# 3_POWER.net
KiCad netlist of a schematic drawn in Altium Designer
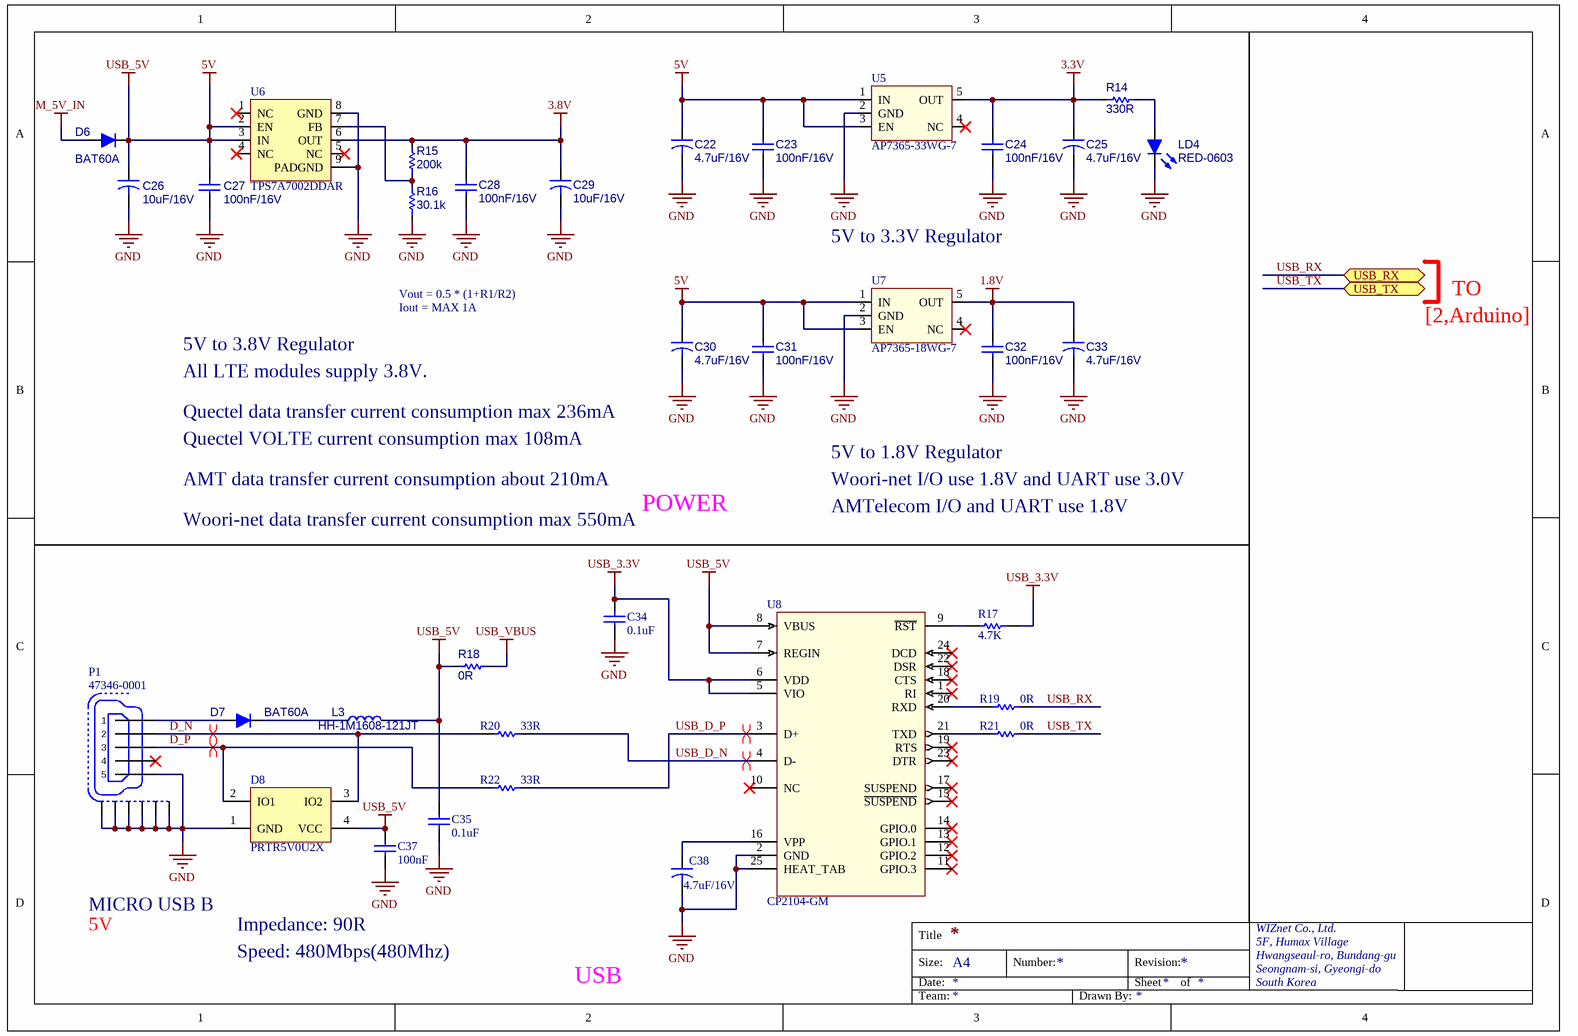
[diagram p0: 3.POWER.SchDoc]

(export (version "E")
  (design (tool "Eeschema 10.0.6"))
  (components
    (comp (ref "C22")
      (value "4.7uF/16V")
      (footprint "CAP-A Size")
      (description "Tantal CAP A Size EIA/IECQ 3216")
      (libsource (lib "Scott_lib") (part "CAP-A Size"))
    )
    (comp (ref "C23")
      (value "100nF/16V")
      (footprint "CAP-0603")
      (description "Ceramic CAP 0603(1608)")
      (libsource (lib "Scott_lib") (part "CAP-0603"))
    )
    (comp (ref "C24")
      (value "100nF/16V")
      (footprint "CAP-0603")
      (description "Ceramic CAP 0603(1608)")
      (libsource (lib "Scott_lib") (part "CAP-0603"))
    )
    (comp (ref "C25")
      (value "4.7uF/16V")
      (footprint "CAP-A Size")
      (description "Tantal CAP A Size EIA/IECQ 3216")
      (libsource (lib "Scott_lib") (part "CAP-A Size"))
    )
    (comp (ref "C26")
      (value "10uF/16V")
      (footprint "CAP-A Size")
      (description "Tantal CAP A Size EIA/IECQ 3216")
      (libsource (lib "Scott_lib") (part "CAP-A Size"))
    )
    (comp (ref "C27")
      (value "100nF/16V")
      (footprint "CAP-0603")
      (description "Ceramic CAP 0603(1608)")
      (libsource (lib "Scott_lib") (part "CAP-0603"))
    )
    (comp (ref "C28")
      (value "100nF/16V")
      (footprint "CAP-0603")
      (description "Ceramic CAP 0603(1608)")
      (libsource (lib "Scott_lib") (part "CAP-0603"))
    )
    (comp (ref "C29")
      (value "10uF/16V")
      (footprint "CAP-A Size")
      (description "Tantal CAP A Size EIA/IECQ 3216")
      (libsource (lib "Scott_lib") (part "CAP-A Size"))
    )
    (comp (ref "C30")
      (value "4.7uF/16V")
      (footprint "CAP-A Size")
      (description "Tantal CAP A Size EIA/IECQ 3216")
      (libsource (lib "Scott_lib") (part "CAP-A Size"))
    )
    (comp (ref "C31")
      (value "100nF/16V")
      (footprint "CAP-0603")
      (description "Ceramic CAP 0603(1608)")
      (libsource (lib "Scott_lib") (part "CAP-0603"))
    )
    (comp (ref "C32")
      (value "100nF/16V")
      (footprint "CAP-0603")
      (description "Ceramic CAP 0603(1608)")
      (libsource (lib "Scott_lib") (part "CAP-0603"))
    )
    (comp (ref "C33")
      (value "4.7uF/16V")
      (footprint "CAP-A Size")
      (description "Tantal CAP A Size EIA/IECQ 3216")
      (libsource (lib "Scott_lib") (part "CAP-A Size"))
    )
    (comp (ref "C34")
      (value "0.1uF")
      (footprint "CAP-0603")
      (description "Ceramic CAP 0603(1608)")
      (libsource (lib "Scott_lib") (part "CAP-0603"))
    )
    (comp (ref "C35")
      (value "0.1uF")
      (footprint "CAP-0603")
      (description "Ceramic CAP 0603(1608)")
      (libsource (lib "Scott_lib") (part "CAP-0603"))
    )
    (comp (ref "C37")
      (value "100nF")
      (footprint "CAP-0603")
      (description "Ceramic CAP 0603(1608)")
      (libsource (lib "Scott_lib") (part "CAP-0603"))
    )
    (comp (ref "C38")
      (value "4.7uF/16V")
      (footprint "CAP-A Size")
      (description "Tantla CAP A Size EIA/IECQ 3216")
      (libsource (lib "Scott_lib") (part "CAP-A Size"))
    )
    (comp (ref "D6")
      (value "BAT60A")
      (footprint "SOD-323(1-C,2-A)")
      (description "Silicon Schottky Diode")
      (libsource (lib "Scott_lib") (part "DIODE-BAT60A"))
    )
    (comp (ref "D7")
      (value "BAT60A")
      (footprint "SOD-323(1-C,2-A)")
      (description "Silicon Schottky Diode")
      (libsource (lib "Scott_lib") (part "DIODE-BAT60A"))
    )
    (comp (ref "D8")
      (value "PRTR5V0U2X")
      (footprint "SOT-143")
      (description "Ultra low capacitance double rail-to-rail ESD protection diode")
      (fields
        (field (name "MANUFACTURER") "NXP")
        (field (name "2ND SOURCE PART NUMBER") "152-4157")
        (field (name "PUBLISHER") "Nordic Semiconductor")
      )
      (libsource (lib "Quectel_IF_Board") (part "PRTR5V0U2X"))
    )
    (comp (ref "L3")
      (value "HH-1M1608-121JT")
      (footprint "IND-0603")
      (description "Inductor 0603(1608)")
      (libsource (lib "Scott_lib") (part "IND-0603"))
    )
    (comp (ref "LD4")
      (value "RED-0603")
      (footprint "LED-0603-RED")
      (description "LED-0603")
      (libsource (lib "Scott_lib") (part "LED-0603"))
    )
    (comp (ref "P1")
      (value "47346-0001")
      (footprint "USB-MOLEX-47346")
      (description "MICRO USB B Type")
      (libsource (lib "Edward") (part "47346-0001"))
    )
    (comp (ref "R14")
      (value "330R")
      (footprint "RES-0402")
      (description "RES-0402")
      (libsource (lib "Scott_lib") (part "RES-0402"))
    )
    (comp (ref "R15")
      (value "200k")
      (footprint "RES-0603")
      (description "RES0603")
      (libsource (lib "") (part "RES-0603_1"))
    )
    (comp (ref "R16")
      (value "30.1k")
      (footprint "RES-0603")
      (description "RES0603")
      (libsource (lib "") (part "RES-0603_1"))
    )
    (comp (ref "R17")
      (value "4.7K")
      (footprint "RES-0603")
      (description "RES-0603")
      (libsource (lib "Scott_lib") (part "RES-0603"))
    )
    (comp (ref "R18")
      (value "0R")
      (footprint "RES-0402")
      (description "RES-0402")
      (libsource (lib "Scott_lib") (part "RES-0402"))
    )
    (comp (ref "R19")
      (value "0R")
      (footprint "RES-0603")
      (description "RES-0603")
      (libsource (lib "Scott_lib") (part "RES-0603"))
    )
    (comp (ref "R20")
      (value "33R")
      (footprint "RES-0603")
      (description "RES-0603")
      (libsource (lib "Scott_lib") (part "RES-0603"))
    )
    (comp (ref "R21")
      (value "0R")
      (footprint "RES-0603")
      (description "RES-0603")
      (libsource (lib "Scott_lib") (part "RES-0603"))
    )
    (comp (ref "R22")
      (value "33R")
      (footprint "RES-0603")
      (description "RES-0603")
      (libsource (lib "Scott_lib") (part "RES-0603"))
    )
    (comp (ref "U5")
      (value "AP7365-33WG-7")
      (footprint "SOT-25")
      (description "3.3V 600mA Regulator/SOT25(Fixed Output)")
      (libsource (lib "Edward") (part "AP7365-33WG-7"))
    )
    (comp (ref "U6")
      (value "TPS7A7002DDAR")
      (footprint "SO-08-EP")
      (libsource (lib "Edward") (part "TPS7A7002DDAR"))
    )
    (comp (ref "U7")
      (value "AP7365-18WG-7")
      (footprint "SOT-25")
      (description "3.3V 600mA Regulator/SOT25(Fixed Output)")
      (libsource (lib "Edward") (part "AP7365-33WG-7"))
    )
    (comp (ref "U8")
      (value "CP2104-GM")
      (footprint "QFN24(0.5/4X4)")
      (description "USB to UART Bridge, SiliconLabs")
      (libsource (lib "Edward") (part "CP2104-GM"))
    )
  )
  (nets
    (net (code "1") (name "/D_N") (class "Default")
      (node (ref "D8") (pin "3") (pinfunction "IO2_3") (pintype "passive"))
      (node (ref "P1") (pin "2") (pinfunction "2_2") (pintype "passive"))
      (node (ref "R20") (pin "1") (pinfunction "1_1") (pintype "passive"))
    )
    (net (code "2") (name "/D_P") (class "Default")
      (node (ref "D8") (pin "2") (pinfunction "IO1_2") (pintype "passive"))
      (node (ref "P1") (pin "3") (pinfunction "3_3") (pintype "passive"))
      (node (ref "R22") (pin "1") (pinfunction "1_1") (pintype "passive"))
    )
    (net (code "3") (name "/USB_D_N") (class "Default")
      (node (ref "R20") (pin "2") (pinfunction "2_2") (pintype "passive"))
      (node (ref "U8") (pin "4") (pinfunction "D-_4") (pintype "passive"))
    )
    (net (code "4") (name "/USB_D_P") (class "Default")
      (node (ref "R22") (pin "2") (pinfunction "2_2") (pintype "passive"))
      (node (ref "U8") (pin "3") (pinfunction "D+_3") (pintype "passive"))
    )
    (net (code "5") (name "/USB_RX") (class "Default")
      (node (ref "R19") (pin "2") (pinfunction "2_2") (pintype "passive"))
    )
    (net (code "6") (name "/USB_TX") (class "Default")
      (node (ref "R21") (pin "2") (pinfunction "2_2") (pintype "passive"))
    )
    (net (code "7") (name "1.8V") (class "Default")
      (node (ref "C32") (pin "2") (pinfunction "2_2") (pintype "passive"))
      (node (ref "C33") (pin "1") (pinfunction "1_1") (pintype "passive"))
      (node (ref "U7") (pin "5") (pinfunction "OUT_5") (pintype "passive"))
    )
    (net (code "8") (name "3.3V") (class "Default")
      (node (ref "C24") (pin "2") (pinfunction "2_2") (pintype "passive"))
      (node (ref "C25") (pin "1") (pinfunction "1_1") (pintype "passive"))
      (node (ref "R14") (pin "1") (pinfunction "1_1") (pintype "passive"))
      (node (ref "U5") (pin "5") (pinfunction "OUT_5") (pintype "passive"))
    )
    (net (code "9") (name "3.8V") (class "Default")
      (node (ref "C28") (pin "2") (pinfunction "2_2") (pintype "passive"))
      (node (ref "C29") (pin "1") (pinfunction "1_1") (pintype "passive"))
      (node (ref "R15") (pin "2") (pinfunction "2_2") (pintype "passive"))
      (node (ref "U6") (pin "6") (pinfunction "OUT_6") (pintype "passive"))
    )
    (net (code "10") (name "5V") (class "Default")
      (node (ref "C22") (pin "1") (pinfunction "1_1") (pintype "passive"))
      (node (ref "C23") (pin "2") (pinfunction "2_2") (pintype "passive"))
      (node (ref "C26") (pin "1") (pinfunction "1_1") (pintype "passive"))
      (node (ref "C27") (pin "2") (pinfunction "2_2") (pintype "passive"))
      (node (ref "C30") (pin "1") (pinfunction "1_1") (pintype "passive"))
      (node (ref "C31") (pin "2") (pinfunction "2_2") (pintype "passive"))
      (node (ref "C35") (pin "2") (pinfunction "2_2") (pintype "passive"))
      (node (ref "C37") (pin "2") (pinfunction "2_2") (pintype "passive"))
      (node (ref "D6") (pin "1") (pinfunction "K_1") (pintype "passive"))
      (node (ref "D8") (pin "4") (pinfunction "VCC_4") (pintype "passive"))
      (node (ref "L3") (pin "2") (pinfunction "2_2") (pintype "passive"))
      (node (ref "R18") (pin "1") (pinfunction "1_1") (pintype "passive"))
      (node (ref "U5") (pin "1") (pinfunction "IN_1") (pintype "passive"))
      (node (ref "U5") (pin "3") (pinfunction "EN_3") (pintype "passive"))
      (node (ref "U6") (pin "2") (pinfunction "EN_2") (pintype "passive"))
      (node (ref "U6") (pin "3") (pinfunction "IN_3") (pintype "passive"))
      (node (ref "U7") (pin "1") (pinfunction "IN_1") (pintype "passive"))
      (node (ref "U7") (pin "3") (pinfunction "EN_3") (pintype "passive"))
      (node (ref "U8") (pin "7") (pinfunction "REGIN_7") (pintype "input"))
      (node (ref "U8") (pin "8") (pinfunction "VBUS_8") (pintype "input"))
    )
    (net (code "11") (name "GND") (class "Default")
      (node (ref "C22") (pin "2") (pinfunction "2_2") (pintype "passive"))
      (node (ref "C23") (pin "1") (pinfunction "1_1") (pintype "passive"))
      (node (ref "C24") (pin "1") (pinfunction "1_1") (pintype "passive"))
      (node (ref "C25") (pin "2") (pinfunction "2_2") (pintype "passive"))
      (node (ref "C26") (pin "2") (pinfunction "2_2") (pintype "passive"))
      (node (ref "C27") (pin "1") (pinfunction "1_1") (pintype "passive"))
      (node (ref "C28") (pin "1") (pinfunction "1_1") (pintype "passive"))
      (node (ref "C29") (pin "2") (pinfunction "2_2") (pintype "passive"))
      (node (ref "C30") (pin "2") (pinfunction "2_2") (pintype "passive"))
      (node (ref "C31") (pin "1") (pinfunction "1_1") (pintype "passive"))
      (node (ref "C32") (pin "1") (pinfunction "1_1") (pintype "passive"))
      (node (ref "C33") (pin "2") (pinfunction "2_2") (pintype "passive"))
      (node (ref "C34") (pin "1") (pinfunction "1_1") (pintype "passive"))
      (node (ref "C35") (pin "1") (pinfunction "1_1") (pintype "passive"))
      (node (ref "C37") (pin "1") (pinfunction "1_1") (pintype "passive"))
      (node (ref "C38") (pin "2") (pinfunction "2_2") (pintype "passive"))
      (node (ref "D8") (pin "1") (pinfunction "GND_1") (pintype "passive"))
      (node (ref "LD4") (pin "2") (pinfunction "K_2") (pintype "passive"))
      (node (ref "P1") (pin "10") (pinfunction "10_10") (pintype "passive"))
      (node (ref "P1") (pin "11") (pinfunction "11_11") (pintype "passive"))
      (node (ref "P1") (pin "5") (pinfunction "5_5") (pintype "passive"))
      (node (ref "P1") (pin "6") (pinfunction "6_6") (pintype "passive"))
      (node (ref "P1") (pin "7") (pinfunction "7_7") (pintype "passive"))
      (node (ref "P1") (pin "8") (pinfunction "8_8") (pintype "passive"))
      (node (ref "P1") (pin "9") (pinfunction "9_9") (pintype "passive"))
      (node (ref "R16") (pin "1") (pinfunction "1_1") (pintype "passive"))
      (node (ref "U5") (pin "2") (pinfunction "GND_2") (pintype "passive"))
      (node (ref "U6") (pin "8") (pinfunction "GND_8") (pintype "passive"))
      (node (ref "U6") (pin "9") (pinfunction "PADGND_9") (pintype "passive"))
      (node (ref "U7") (pin "2") (pinfunction "GND_2") (pintype "passive"))
      (node (ref "U8") (pin "2") (pinfunction "GND_2") (pintype "power_in"))
      (node (ref "U8") (pin "25") (pinfunction "HEAT_TAB_25") (pintype "passive"))
    )
    (net (code "12") (name "M_5V_IN") (class "Default")
      (node (ref "D6") (pin "2") (pinfunction "A_2") (pintype "passive"))
    )
    (net (code "13") (name "Net-(D7-A)") (class "Default")
      (node (ref "D7") (pin "2") (pinfunction "A_2") (pintype "passive"))
      (node (ref "P1") (pin "1") (pinfunction "1_1") (pintype "passive"))
    )
    (net (code "14") (name "Net-(D7-K)") (class "Default")
      (node (ref "D7") (pin "1") (pinfunction "K_1") (pintype "passive"))
      (node (ref "L3") (pin "1") (pinfunction "1_1") (pintype "passive"))
    )
    (net (code "15") (name "Net-(LD4-A)") (class "Default")
      (node (ref "LD4") (pin "1") (pinfunction "A_1") (pintype "passive"))
      (node (ref "R14") (pin "2") (pinfunction "2_2") (pintype "passive"))
    )
    (net (code "16") (name "Net-(U6-FB)") (class "Default")
      (node (ref "R15") (pin "1") (pinfunction "1_1") (pintype "passive"))
      (node (ref "R16") (pin "2") (pinfunction "2_2") (pintype "passive"))
      (node (ref "U6") (pin "7") (pinfunction "FB_7") (pintype "passive"))
    )
    (net (code "17") (name "Net-(U8-RST)") (class "Default")
      (node (ref "R17") (pin "1") (pinfunction "1_1") (pintype "passive"))
      (node (ref "U8") (pin "9") (pinfunction "RST_9") (pintype "passive"))
    )
    (net (code "18") (name "Net-(U8-RXD)") (class "Default")
      (node (ref "R19") (pin "1") (pinfunction "1_1") (pintype "passive"))
      (node (ref "U8") (pin "20") (pinfunction "RXD_20") (pintype "input"))
    )
    (net (code "19") (name "Net-(U8-TXD)") (class "Default")
      (node (ref "R21") (pin "1") (pinfunction "1_1") (pintype "passive"))
      (node (ref "U8") (pin "21") (pinfunction "TXD_21") (pintype "output"))
    )
    (net (code "20") (name "Net-(U8-VPP)") (class "Default")
      (node (ref "C38") (pin "1") (pinfunction "1_1") (pintype "passive"))
      (node (ref "U8") (pin "16") (pinfunction "VPP_16") (pintype "passive"))
    )
    (net (code "21") (name "USB_3.3V") (class "Default")
      (node (ref "C34") (pin "2") (pinfunction "2_2") (pintype "passive"))
      (node (ref "R17") (pin "2") (pinfunction "2_2") (pintype "passive"))
      (node (ref "U8") (pin "5") (pinfunction "VIO_5") (pintype "power_in"))
      (node (ref "U8") (pin "6") (pinfunction "VDD_6") (pintype "power_in"))
    )
    (net (code "22") (name "USB_VBUS") (class "Default")
      (node (ref "R18") (pin "2") (pinfunction "2_2") (pintype "passive"))
    )
    (net (code "23") (name "unconnected-(P1-Pad4)") (class "Default")
      (node (ref "P1") (pin "4") (pinfunction "4_4") (pintype "passive+no_connect"))
    )
    (net (code "24") (name "unconnected-(U5-NC-Pad4)") (class "Default")
      (node (ref "U5") (pin "4") (pinfunction "NC_4") (pintype "passive+no_connect"))
    )
    (net (code "25") (name "unconnected-(U6-NC-Pad1)") (class "Default")
      (node (ref "U6") (pin "1") (pinfunction "NC_1") (pintype "passive+no_connect"))
    )
    (net (code "26") (name "unconnected-(U6-NC-Pad4)") (class "Default")
      (node (ref "U6") (pin "4") (pinfunction "NC_4") (pintype "passive+no_connect"))
    )
    (net (code "27") (name "unconnected-(U6-NC-Pad5)") (class "Default")
      (node (ref "U6") (pin "5") (pinfunction "NC_5") (pintype "passive+no_connect"))
    )
    (net (code "28") (name "unconnected-(U7-NC-Pad4)") (class "Default")
      (node (ref "U7") (pin "4") (pinfunction "NC_4") (pintype "passive+no_connect"))
    )
    (net (code "29") (name "unconnected-(U8-CTS-Pad18)") (class "Default")
      (node (ref "U8") (pin "18") (pinfunction "CTS_18") (pintype "input+no_connect"))
    )
    (net (code "30") (name "unconnected-(U8-DCD-Pad24)") (class "Default")
      (node (ref "U8") (pin "24") (pinfunction "DCD_24") (pintype "input+no_connect"))
    )
    (net (code "31") (name "unconnected-(U8-DSR-Pad22)") (class "Default")
      (node (ref "U8") (pin "22") (pinfunction "DSR_22") (pintype "input+no_connect"))
    )
    (net (code "32") (name "unconnected-(U8-DTR-Pad23)") (class "Default")
      (node (ref "U8") (pin "23") (pinfunction "DTR_23") (pintype "output+no_connect"))
    )
    (net (code "33") (name "unconnected-(U8-GPIO.0-Pad14)") (class "Default")
      (node (ref "U8") (pin "14") (pinfunction "GPIO.0_14") (pintype "passive+no_connect"))
    )
    (net (code "34") (name "unconnected-(U8-GPIO.1-Pad13)") (class "Default")
      (node (ref "U8") (pin "13") (pinfunction "GPIO.1_13") (pintype "passive+no_connect"))
    )
    (net (code "35") (name "unconnected-(U8-GPIO.2-Pad12)") (class "Default")
      (node (ref "U8") (pin "12") (pinfunction "GPIO.2_12") (pintype "passive+no_connect"))
    )
    (net (code "36") (name "unconnected-(U8-GPIO.3-Pad11)") (class "Default")
      (node (ref "U8") (pin "11") (pinfunction "GPIO.3_11") (pintype "passive+no_connect"))
    )
    (net (code "37") (name "unconnected-(U8-NC-Pad10)") (class "Default")
      (node (ref "U8") (pin "10") (pinfunction "NC_10") (pintype "passive+no_connect"))
    )
    (net (code "38") (name "unconnected-(U8-RI-Pad1)") (class "Default")
      (node (ref "U8") (pin "1") (pinfunction "RI_1") (pintype "input+no_connect"))
    )
    (net (code "39") (name "unconnected-(U8-RTS-Pad19)") (class "Default")
      (node (ref "U8") (pin "19") (pinfunction "RTS_19") (pintype "output+no_connect"))
    )
    (net (code "40") (name "unconnected-(U8-SUSPEND-Pad15)") (class "Default")
      (node (ref "U8") (pin "15") (pinfunction "SUSPEND_15") (pintype "output+no_connect"))
    )
    (net (code "41") (name "unconnected-(U8-SUSPEND-Pad17)") (class "Default")
      (node (ref "U8") (pin "17") (pinfunction "SUSPEND_17") (pintype "output+no_connect"))
    )
  )
)
